# hub-carrier.net
KiCad netlist of a schematic drawn in EAGLE
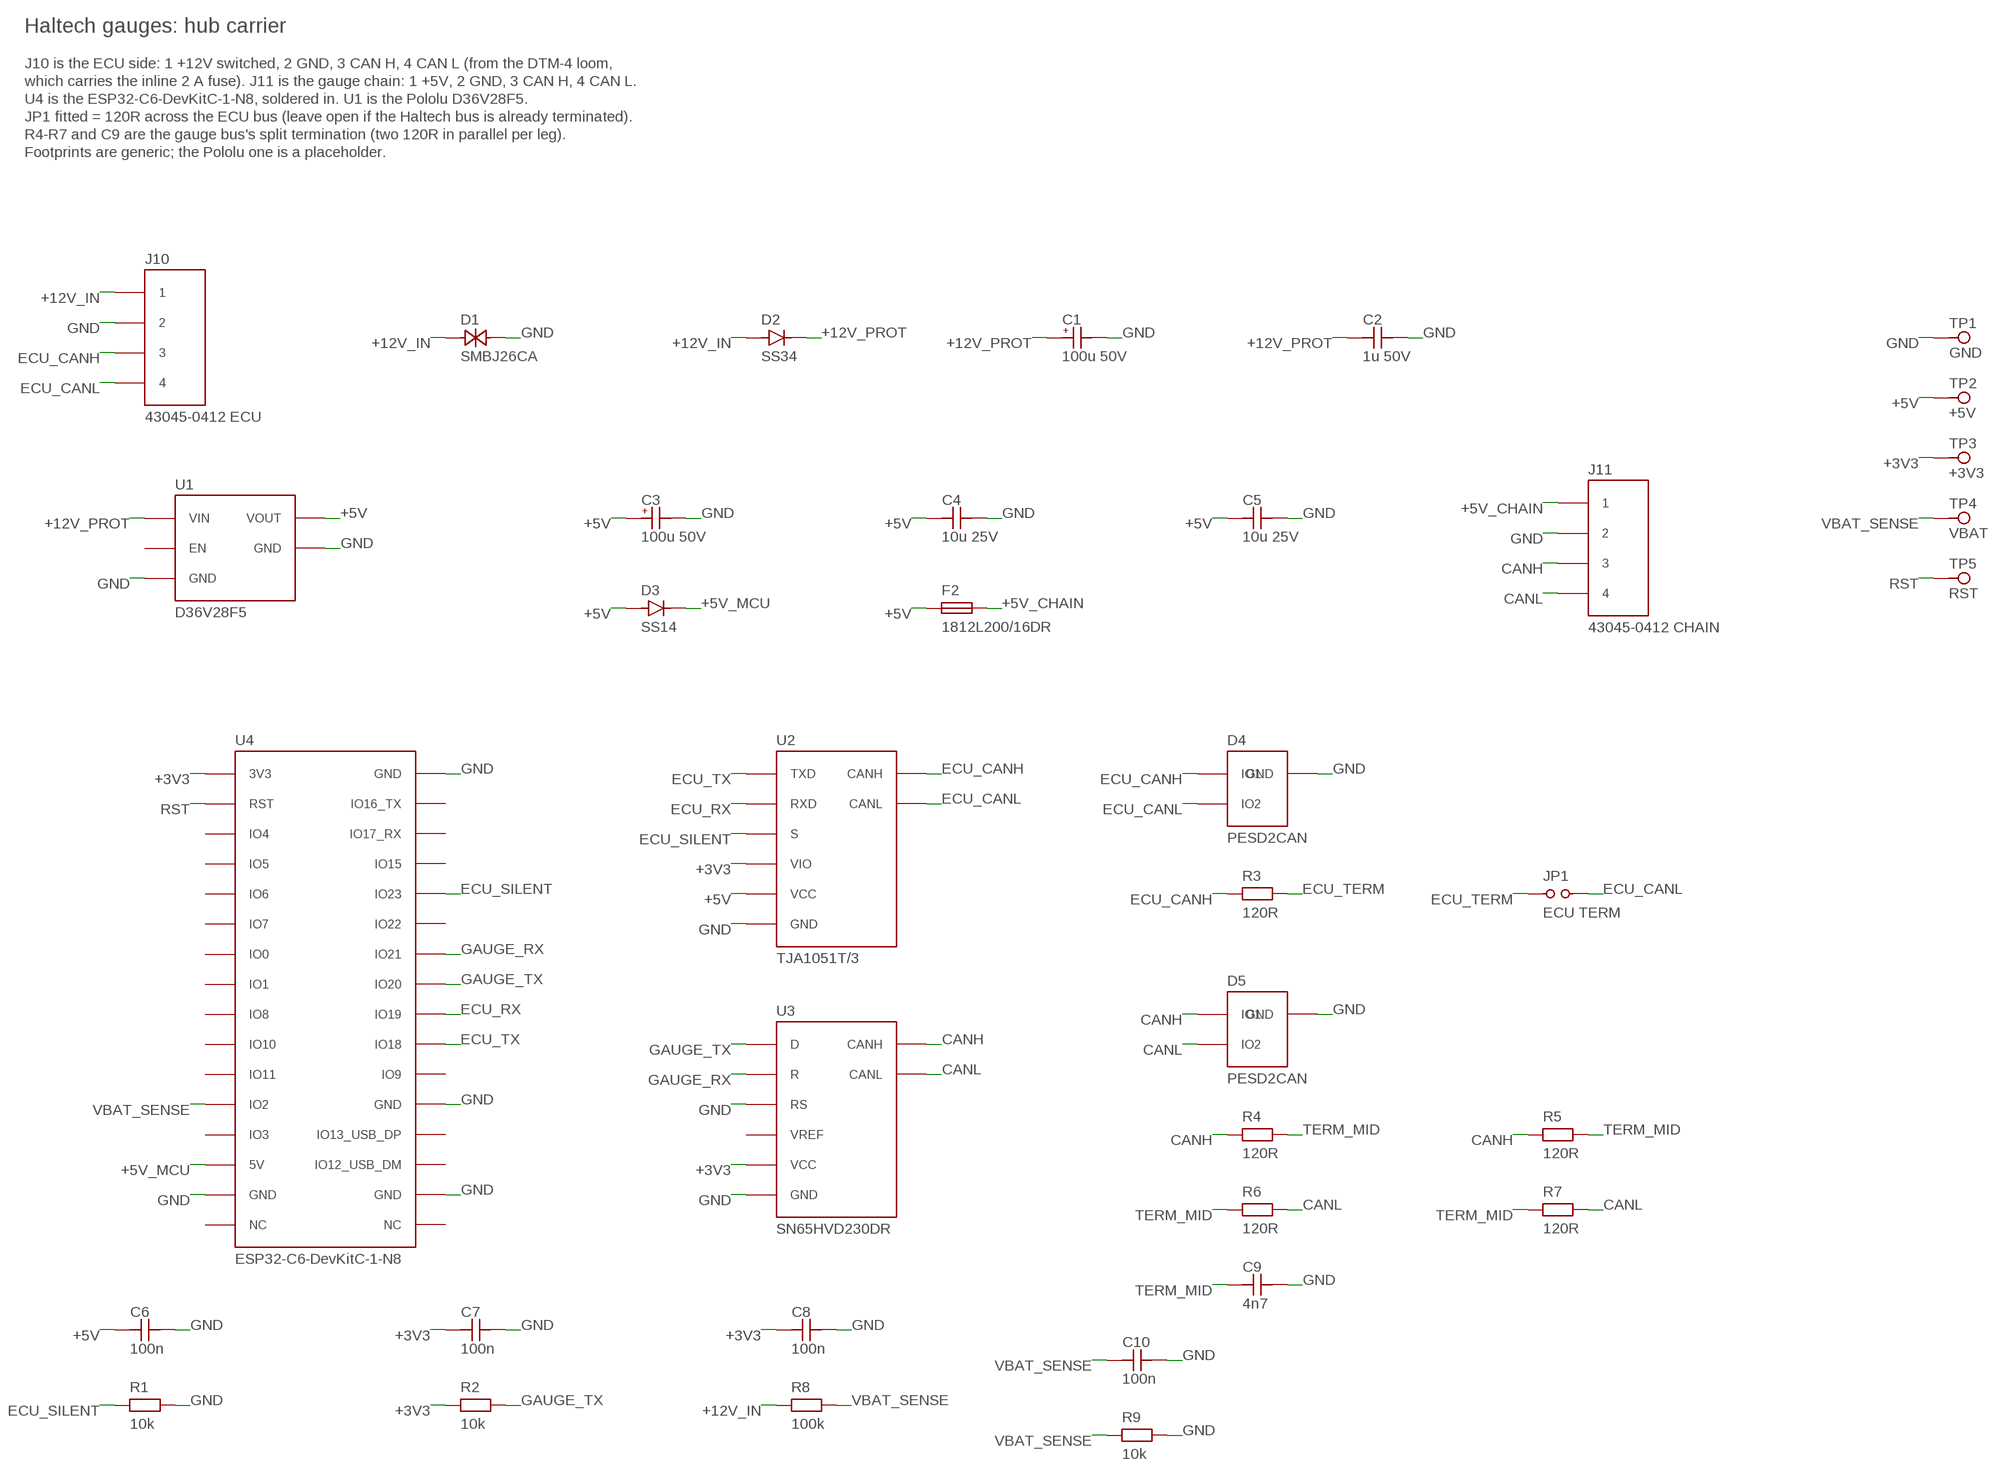
[diagram p0: schematic, sheet 1]

(export (version "E")
  (design (tool "Eeschema 10.0.6"))
  (components
    (comp (ref "C1")
      (value "100u 50V")
      (footprint "eagle-import:CAP-SMD-8X10")
      (fields (field (name "LCSC") "C116241"))
      (libsource (lib "eagle-import") (part "CPOL-8X10"))
    )
    (comp (ref "C2")
      (value "1u 50V")
      (footprint "eagle-import:0805")
      (fields (field (name "LCSC") "C28323"))
      (libsource (lib "eagle-import") (part "C0805"))
    )
    (comp (ref "C3")
      (value "100u 50V")
      (footprint "eagle-import:CAP-SMD-8X10")
      (fields (field (name "LCSC") "C116241"))
      (libsource (lib "eagle-import") (part "CPOL-8X10"))
    )
    (comp (ref "C4")
      (value "10u 25V")
      (footprint "eagle-import:0805")
      (fields (field (name "LCSC") "C15850"))
      (libsource (lib "eagle-import") (part "C0805"))
    )
    (comp (ref "C5")
      (value "10u 25V")
      (footprint "eagle-import:0805")
      (fields (field (name "LCSC") "C15850"))
      (libsource (lib "eagle-import") (part "C0805"))
    )
    (comp (ref "C6")
      (value "100n")
      (footprint "eagle-import:0805")
      (fields (field (name "LCSC") "C49678"))
      (libsource (lib "eagle-import") (part "C0805"))
    )
    (comp (ref "C7")
      (value "100n")
      (footprint "eagle-import:0805")
      (fields (field (name "LCSC") "C49678"))
      (libsource (lib "eagle-import") (part "C0805"))
    )
    (comp (ref "C8")
      (value "100n")
      (footprint "eagle-import:0805")
      (fields (field (name "LCSC") "C49678"))
      (libsource (lib "eagle-import") (part "C0805"))
    )
    (comp (ref "C9")
      (value "4n7")
      (footprint "eagle-import:0805")
      (fields (field (name "LCSC") "C1744"))
      (libsource (lib "eagle-import") (part "C0805"))
    )
    (comp (ref "C10")
      (value "100n")
      (footprint "eagle-import:0805")
      (fields (field (name "LCSC") "C49678"))
      (libsource (lib "eagle-import") (part "C0805"))
    )
    (comp (ref "D1")
      (value "SMBJ26CA")
      (footprint "eagle-import:SMB")
      (fields (field (name "LCSC") "C515606"))
      (libsource (lib "eagle-import") (part "TVS-SMB"))
    )
    (comp (ref "D2")
      (value "SS34")
      (footprint "eagle-import:SMA")
      (fields (field (name "LCSC") "C8678"))
      (libsource (lib "eagle-import") (part "SCHOTTKY-SMA"))
    )
    (comp (ref "D3")
      (value "SS14")
      (footprint "eagle-import:SMA")
      (fields (field (name "LCSC") "C2480"))
      (libsource (lib "eagle-import") (part "SCHOTTKY-SMA"))
    )
    (comp (ref "D4")
      (value "PESD2CAN")
      (footprint "eagle-import:SOT23")
      (fields (field (name "LCSC") "C75176"))
      (libsource (lib "eagle-import") (part "PESD2CAN"))
    )
    (comp (ref "D5")
      (value "PESD2CAN")
      (footprint "eagle-import:SOT23")
      (fields (field (name "LCSC") "C75176"))
      (libsource (lib "eagle-import") (part "PESD2CAN"))
    )
    (comp (ref "F2")
      (value "1812L200/16DR")
      (footprint "eagle-import:1812")
      (fields (field (name "LCSC") "C439873"))
      (libsource (lib "eagle-import") (part "POLYFUSE-1812"))
    )
    (comp (ref "J10")
      (value "43045-0412 ECU")
      (footprint "eagle-import:MOLEX-43045-0412")
      (libsource (lib "eagle-import") (part "MICROFIT-2X2"))
    )
    (comp (ref "J11")
      (value "43045-0412 CHAIN")
      (footprint "eagle-import:MOLEX-43045-0412")
      (libsource (lib "eagle-import") (part "MICROFIT-2X2"))
    )
    (comp (ref "JP1")
      (value "ECU TERM")
      (footprint "eagle-import:HDR-1X2")
      (libsource (lib "eagle-import") (part "JUMPER-2"))
    )
    (comp (ref "R1")
      (value "10k")
      (footprint "eagle-import:0805")
      (fields (field (name "LCSC") "C17414"))
      (libsource (lib "eagle-import") (part "R0805"))
    )
    (comp (ref "R2")
      (value "10k")
      (footprint "eagle-import:0805")
      (fields (field (name "LCSC") "C17414"))
      (libsource (lib "eagle-import") (part "R0805"))
    )
    (comp (ref "R3")
      (value "120R")
      (footprint "eagle-import:1206")
      (fields (field (name "LCSC") "C17909"))
      (libsource (lib "eagle-import") (part "R1206"))
    )
    (comp (ref "R4")
      (value "120R")
      (footprint "eagle-import:1206")
      (fields (field (name "LCSC") "C17909"))
      (libsource (lib "eagle-import") (part "R1206"))
    )
    (comp (ref "R5")
      (value "120R")
      (footprint "eagle-import:1206")
      (fields (field (name "LCSC") "C17909"))
      (libsource (lib "eagle-import") (part "R1206"))
    )
    (comp (ref "R6")
      (value "120R")
      (footprint "eagle-import:1206")
      (fields (field (name "LCSC") "C17909"))
      (libsource (lib "eagle-import") (part "R1206"))
    )
    (comp (ref "R7")
      (value "120R")
      (footprint "eagle-import:1206")
      (fields (field (name "LCSC") "C17909"))
      (libsource (lib "eagle-import") (part "R1206"))
    )
    (comp (ref "R8")
      (value "100k")
      (footprint "eagle-import:0805")
      (fields (field (name "LCSC") "C149504"))
      (libsource (lib "eagle-import") (part "R0805"))
    )
    (comp (ref "R9")
      (value "10k")
      (footprint "eagle-import:0805")
      (fields (field (name "LCSC") "C17414"))
      (libsource (lib "eagle-import") (part "R0805"))
    )
    (comp (ref "TP1")
      (value "GND")
      (footprint "eagle-import:TESTPAD")
      (libsource (lib "eagle-import") (part "TESTPOINT"))
    )
    (comp (ref "TP2")
      (value "+5V")
      (footprint "eagle-import:TESTPAD")
      (libsource (lib "eagle-import") (part "TESTPOINT"))
    )
    (comp (ref "TP3")
      (value "+3V3")
      (footprint "eagle-import:TESTPAD")
      (libsource (lib "eagle-import") (part "TESTPOINT"))
    )
    (comp (ref "TP4")
      (value "VBAT")
      (footprint "eagle-import:TESTPAD")
      (libsource (lib "eagle-import") (part "TESTPOINT"))
    )
    (comp (ref "TP5")
      (value "RST")
      (footprint "eagle-import:TESTPAD")
      (libsource (lib "eagle-import") (part "TESTPOINT"))
    )
    (comp (ref "U1")
      (value "D36V28F5")
      (footprint "eagle-import:POLOLU-D36V28F-PLACEHOLDER")
      (libsource (lib "eagle-import") (part "POLOLU-D36V28F5"))
    )
    (comp (ref "U2")
      (value "TJA1051T/3")
      (footprint "eagle-import:SOIC8")
      (fields (field (name "LCSC") "C38695"))
      (libsource (lib "eagle-import") (part "TJA1051T-3"))
    )
    (comp (ref "U3")
      (value "SN65HVD230DR")
      (footprint "eagle-import:SOIC8")
      (fields (field (name "LCSC") "C12084"))
      (libsource (lib "eagle-import") (part "SN65HVD230"))
    )
    (comp (ref "U4")
      (value "ESP32-C6-DevKitC-1-N8")
      (footprint "eagle-import:ESP32-C6-DEVKITC-1")
      (libsource (lib "eagle-import") (part "ESP32-C6-DEVKITC-1"))
    )
  )
  (nets
    (net (code "1") (name "/+3V3") (class "Default")
      (node (ref "C7") (pin "1") (pinfunction "1_1") (pintype "passive"))
      (node (ref "C8") (pin "1") (pinfunction "1_1") (pintype "passive"))
      (node (ref "R2") (pin "1") (pinfunction "1_1") (pintype "passive"))
      (node (ref "TP3") (pin "1") (pinfunction "TP_1") (pintype "passive"))
      (node (ref "U2") (pin "5") (pinfunction "VIO_5") (pintype "passive"))
      (node (ref "U3") (pin "3") (pinfunction "VCC_3") (pintype "passive"))
      (node (ref "U4") (pin "J1_1") (pinfunction "3V3_J1_1") (pintype "passive"))
    )
    (net (code "2") (name "/+5V") (class "Default")
      (node (ref "C3") (pin "1") (pinfunction "+_1") (pintype "passive"))
      (node (ref "C4") (pin "1") (pinfunction "1_1") (pintype "passive"))
      (node (ref "C5") (pin "1") (pinfunction "1_1") (pintype "passive"))
      (node (ref "C6") (pin "1") (pinfunction "1_1") (pintype "passive"))
      (node (ref "D3") (pin "2") (pinfunction "A_2") (pintype "passive"))
      (node (ref "F2") (pin "1") (pinfunction "1_1") (pintype "passive"))
      (node (ref "TP2") (pin "1") (pinfunction "TP_1") (pintype "passive"))
      (node (ref "U1") (pin "VOUT") (pinfunction "VOUT_VOUT") (pintype "passive"))
      (node (ref "U2") (pin "3") (pinfunction "VCC_3") (pintype "passive"))
    )
    (net (code "3") (name "/+5V_CHAIN") (class "Default")
      (node (ref "F2") (pin "2") (pinfunction "2_2") (pintype "passive"))
      (node (ref "J11") (pin "1") (pinfunction "1_1") (pintype "passive"))
    )
    (net (code "4") (name "/+5V_MCU") (class "Default")
      (node (ref "D3") (pin "1") (pinfunction "K_1") (pintype "passive"))
      (node (ref "U4") (pin "J1_14") (pinfunction "5V_J1_14") (pintype "passive"))
    )
    (net (code "5") (name "/+12V_IN") (class "Default")
      (node (ref "D1") (pin "1") (pinfunction "1_1") (pintype "passive"))
      (node (ref "D2") (pin "2") (pinfunction "A_2") (pintype "passive"))
      (node (ref "J10") (pin "1") (pinfunction "1_1") (pintype "passive"))
      (node (ref "R8") (pin "1") (pinfunction "1_1") (pintype "passive"))
    )
    (net (code "6") (name "/+12V_PROT") (class "Default")
      (node (ref "C1") (pin "1") (pinfunction "+_1") (pintype "passive"))
      (node (ref "C2") (pin "1") (pinfunction "1_1") (pintype "passive"))
      (node (ref "D2") (pin "1") (pinfunction "K_1") (pintype "passive"))
      (node (ref "U1") (pin "VIN") (pinfunction "VIN_VIN") (pintype "passive"))
    )
    (net (code "7") (name "/CANH") (class "Default")
      (node (ref "D5") (pin "1") (pinfunction "IO1_1") (pintype "passive"))
      (node (ref "J11") (pin "3") (pinfunction "3_3") (pintype "passive"))
      (node (ref "R4") (pin "1") (pinfunction "1_1") (pintype "passive"))
      (node (ref "R5") (pin "1") (pinfunction "1_1") (pintype "passive"))
      (node (ref "U3") (pin "7") (pinfunction "CANH_7") (pintype "passive"))
    )
    (net (code "8") (name "/CANL") (class "Default")
      (node (ref "D5") (pin "2") (pinfunction "IO2_2") (pintype "passive"))
      (node (ref "J11") (pin "4") (pinfunction "4_4") (pintype "passive"))
      (node (ref "R6") (pin "2") (pinfunction "2_2") (pintype "passive"))
      (node (ref "R7") (pin "2") (pinfunction "2_2") (pintype "passive"))
      (node (ref "U3") (pin "6") (pinfunction "CANL_6") (pintype "passive"))
    )
    (net (code "9") (name "/ECU_CANH") (class "Default")
      (node (ref "D4") (pin "1") (pinfunction "IO1_1") (pintype "passive"))
      (node (ref "J10") (pin "3") (pinfunction "3_3") (pintype "passive"))
      (node (ref "R3") (pin "1") (pinfunction "1_1") (pintype "passive"))
      (node (ref "U2") (pin "7") (pinfunction "CANH_7") (pintype "passive"))
    )
    (net (code "10") (name "/ECU_CANL") (class "Default")
      (node (ref "D4") (pin "2") (pinfunction "IO2_2") (pintype "passive"))
      (node (ref "J10") (pin "4") (pinfunction "4_4") (pintype "passive"))
      (node (ref "JP1") (pin "2") (pinfunction "2_2") (pintype "passive"))
      (node (ref "U2") (pin "6") (pinfunction "CANL_6") (pintype "passive"))
    )
    (net (code "11") (name "/ECU_RX") (class "Default")
      (node (ref "U2") (pin "4") (pinfunction "RXD_4") (pintype "passive"))
      (node (ref "U4") (pin "J3_9") (pinfunction "IO19_J3_9") (pintype "passive"))
    )
    (net (code "12") (name "/ECU_SILENT") (class "Default")
      (node (ref "R1") (pin "1") (pinfunction "1_1") (pintype "passive"))
      (node (ref "U2") (pin "8") (pinfunction "S_8") (pintype "passive"))
      (node (ref "U4") (pin "J3_5") (pinfunction "IO23_J3_5") (pintype "passive"))
    )
    (net (code "13") (name "/ECU_TERM") (class "Default")
      (node (ref "JP1") (pin "1") (pinfunction "1_1") (pintype "passive"))
      (node (ref "R3") (pin "2") (pinfunction "2_2") (pintype "passive"))
    )
    (net (code "14") (name "/ECU_TX") (class "Default")
      (node (ref "U2") (pin "1") (pinfunction "TXD_1") (pintype "passive"))
      (node (ref "U4") (pin "J3_10") (pinfunction "IO18_J3_10") (pintype "passive"))
    )
    (net (code "15") (name "/GAUGE_RX") (class "Default")
      (node (ref "U3") (pin "4") (pinfunction "R_4") (pintype "passive"))
      (node (ref "U4") (pin "J3_7") (pinfunction "IO21_J3_7") (pintype "passive"))
    )
    (net (code "16") (name "/GAUGE_TX") (class "Default")
      (node (ref "R2") (pin "2") (pinfunction "2_2") (pintype "passive"))
      (node (ref "U3") (pin "1") (pinfunction "D_1") (pintype "passive"))
      (node (ref "U4") (pin "J3_8") (pinfunction "IO20_J3_8") (pintype "passive"))
    )
    (net (code "17") (name "/GND") (class "Default")
      (node (ref "C1") (pin "2") (pinfunction "-_2") (pintype "passive"))
      (node (ref "C10") (pin "2") (pinfunction "2_2") (pintype "passive"))
      (node (ref "C2") (pin "2") (pinfunction "2_2") (pintype "passive"))
      (node (ref "C3") (pin "2") (pinfunction "-_2") (pintype "passive"))
      (node (ref "C4") (pin "2") (pinfunction "2_2") (pintype "passive"))
      (node (ref "C5") (pin "2") (pinfunction "2_2") (pintype "passive"))
      (node (ref "C6") (pin "2") (pinfunction "2_2") (pintype "passive"))
      (node (ref "C7") (pin "2") (pinfunction "2_2") (pintype "passive"))
      (node (ref "C8") (pin "2") (pinfunction "2_2") (pintype "passive"))
      (node (ref "C9") (pin "2") (pinfunction "2_2") (pintype "passive"))
      (node (ref "D1") (pin "2") (pinfunction "2_2") (pintype "passive"))
      (node (ref "D4") (pin "3") (pinfunction "GND_3") (pintype "passive"))
      (node (ref "D5") (pin "3") (pinfunction "GND_3") (pintype "passive"))
      (node (ref "J10") (pin "2") (pinfunction "2_2") (pintype "passive"))
      (node (ref "J11") (pin "2") (pinfunction "2_2") (pintype "passive"))
      (node (ref "R1") (pin "2") (pinfunction "2_2") (pintype "passive"))
      (node (ref "R9") (pin "2") (pinfunction "2_2") (pintype "passive"))
      (node (ref "TP1") (pin "1") (pinfunction "TP_1") (pintype "passive"))
      (node (ref "U1") (pin "GND1") (pinfunction "GND_GND1") (pintype "passive"))
      (node (ref "U1") (pin "GND2") (pinfunction "GND_GND2") (pintype "passive"))
      (node (ref "U2") (pin "2") (pinfunction "GND_2") (pintype "passive"))
      (node (ref "U3") (pin "2") (pinfunction "GND_2") (pintype "passive"))
      (node (ref "U3") (pin "8") (pinfunction "RS_8") (pintype "passive"))
      (node (ref "U4") (pin "J1_15") (pinfunction "GND_J1_15") (pintype "passive"))
      (node (ref "U4") (pin "J3_1") (pinfunction "GND_J3_1") (pintype "passive"))
      (node (ref "U4") (pin "J3_12") (pinfunction "GND_J3_12") (pintype "passive"))
      (node (ref "U4") (pin "J3_15") (pinfunction "GND_J3_15") (pintype "passive"))
    )
    (net (code "18") (name "/RST") (class "Default")
      (node (ref "TP5") (pin "1") (pinfunction "TP_1") (pintype "passive"))
      (node (ref "U4") (pin "J1_2") (pinfunction "RST_J1_2") (pintype "passive"))
    )
    (net (code "19") (name "/TERM_MID") (class "Default")
      (node (ref "C9") (pin "1") (pinfunction "1_1") (pintype "passive"))
      (node (ref "R4") (pin "2") (pinfunction "2_2") (pintype "passive"))
      (node (ref "R5") (pin "2") (pinfunction "2_2") (pintype "passive"))
      (node (ref "R6") (pin "1") (pinfunction "1_1") (pintype "passive"))
      (node (ref "R7") (pin "1") (pinfunction "1_1") (pintype "passive"))
    )
    (net (code "20") (name "/VBAT_SENSE") (class "Default")
      (node (ref "C10") (pin "1") (pinfunction "1_1") (pintype "passive"))
      (node (ref "R8") (pin "2") (pinfunction "2_2") (pintype "passive"))
      (node (ref "R9") (pin "1") (pinfunction "1_1") (pintype "passive"))
      (node (ref "TP4") (pin "1") (pinfunction "TP_1") (pintype "passive"))
      (node (ref "U4") (pin "J1_12") (pinfunction "IO2_J1_12") (pintype "passive"))
    )
    (net (code "21") (name "unconnected-(U1-PadEN)") (class "Default")
      (node (ref "U1") (pin "EN") (pinfunction "EN_EN") (pintype "passive"))
    )
    (net (code "22") (name "unconnected-(U3-VREF-Pad5)") (class "Default")
      (node (ref "U3") (pin "5") (pinfunction "VREF_5") (pintype "passive"))
    )
    (net (code "23") (name "unconnected-(U4-IO0-PadJ1_7)") (class "Default")
      (node (ref "U4") (pin "J1_7") (pinfunction "IO0_J1_7") (pintype "passive"))
    )
    (net (code "24") (name "unconnected-(U4-IO1-PadJ1_8)") (class "Default")
      (node (ref "U4") (pin "J1_8") (pinfunction "IO1_J1_8") (pintype "passive"))
    )
    (net (code "25") (name "unconnected-(U4-IO3-PadJ1_13)") (class "Default")
      (node (ref "U4") (pin "J1_13") (pinfunction "IO3_J1_13") (pintype "passive"))
    )
    (net (code "26") (name "unconnected-(U4-IO4-PadJ1_3)") (class "Default")
      (node (ref "U4") (pin "J1_3") (pinfunction "IO4_J1_3") (pintype "passive"))
    )
    (net (code "27") (name "unconnected-(U4-IO5-PadJ1_4)") (class "Default")
      (node (ref "U4") (pin "J1_4") (pinfunction "IO5_J1_4") (pintype "passive"))
    )
    (net (code "28") (name "unconnected-(U4-IO6-PadJ1_5)") (class "Default")
      (node (ref "U4") (pin "J1_5") (pinfunction "IO6_J1_5") (pintype "passive"))
    )
    (net (code "29") (name "unconnected-(U4-IO7-PadJ1_6)") (class "Default")
      (node (ref "U4") (pin "J1_6") (pinfunction "IO7_J1_6") (pintype "passive"))
    )
    (net (code "30") (name "unconnected-(U4-IO8-PadJ1_9)") (class "Default")
      (node (ref "U4") (pin "J1_9") (pinfunction "IO8_J1_9") (pintype "passive"))
    )
    (net (code "31") (name "unconnected-(U4-IO9-PadJ3_11)") (class "Default")
      (node (ref "U4") (pin "J3_11") (pinfunction "IO9_J3_11") (pintype "passive"))
    )
    (net (code "32") (name "unconnected-(U4-IO10-PadJ1_10)") (class "Default")
      (node (ref "U4") (pin "J1_10") (pinfunction "IO10_J1_10") (pintype "passive"))
    )
    (net (code "33") (name "unconnected-(U4-IO11-PadJ1_11)") (class "Default")
      (node (ref "U4") (pin "J1_11") (pinfunction "IO11_J1_11") (pintype "passive"))
    )
    (net (code "34") (name "unconnected-(U4-IO12_USB_DM-PadJ3_14)") (class "Default")
      (node (ref "U4") (pin "J3_14") (pinfunction "IO12_USB_DM_J3_14") (pintype "passive"))
    )
    (net (code "35") (name "unconnected-(U4-IO13_USB_DP-PadJ3_13)") (class "Default")
      (node (ref "U4") (pin "J3_13") (pinfunction "IO13_USB_DP_J3_13") (pintype "passive"))
    )
    (net (code "36") (name "unconnected-(U4-IO15-PadJ3_4)") (class "Default")
      (node (ref "U4") (pin "J3_4") (pinfunction "IO15_J3_4") (pintype "passive"))
    )
    (net (code "37") (name "unconnected-(U4-IO16_TX-PadJ3_2)") (class "Default")
      (node (ref "U4") (pin "J3_2") (pinfunction "IO16_TX_J3_2") (pintype "passive"))
    )
    (net (code "38") (name "unconnected-(U4-IO17_RX-PadJ3_3)") (class "Default")
      (node (ref "U4") (pin "J3_3") (pinfunction "IO17_RX_J3_3") (pintype "passive"))
    )
    (net (code "39") (name "unconnected-(U4-IO22-PadJ3_6)") (class "Default")
      (node (ref "U4") (pin "J3_6") (pinfunction "IO22_J3_6") (pintype "passive"))
    )
    (net (code "40") (name "unconnected-(U4-NC-PadJ1_16)") (class "Default")
      (node (ref "U4") (pin "J1_16") (pinfunction "NC_J1_16") (pintype "passive"))
    )
    (net (code "41") (name "unconnected-(U4-NC-PadJ3_16)") (class "Default")
      (node (ref "U4") (pin "J3_16") (pinfunction "NC_J3_16") (pintype "passive"))
    )
  )
)
